# classd.net
KiCad netlist of a schematic drawn in EAGLE
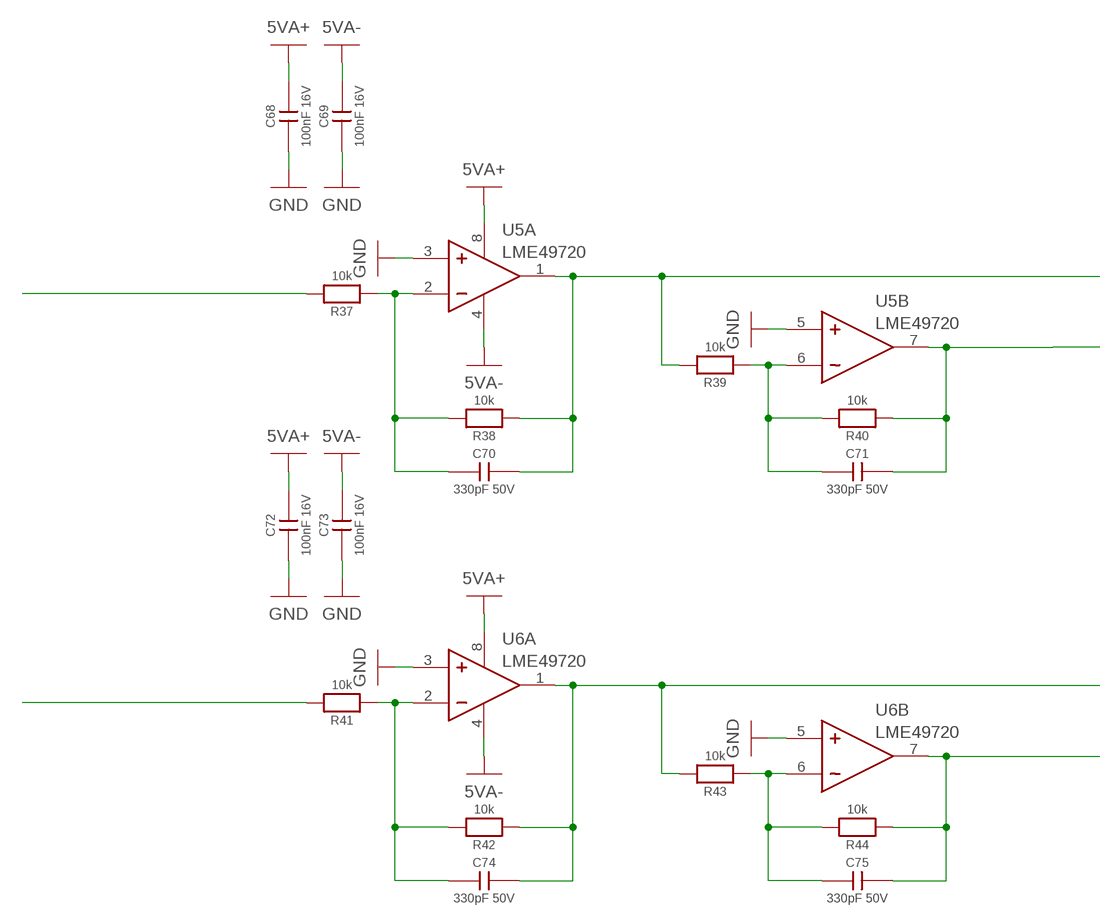
[diagram p0: schematic, sheet 1, part 1 of 2]
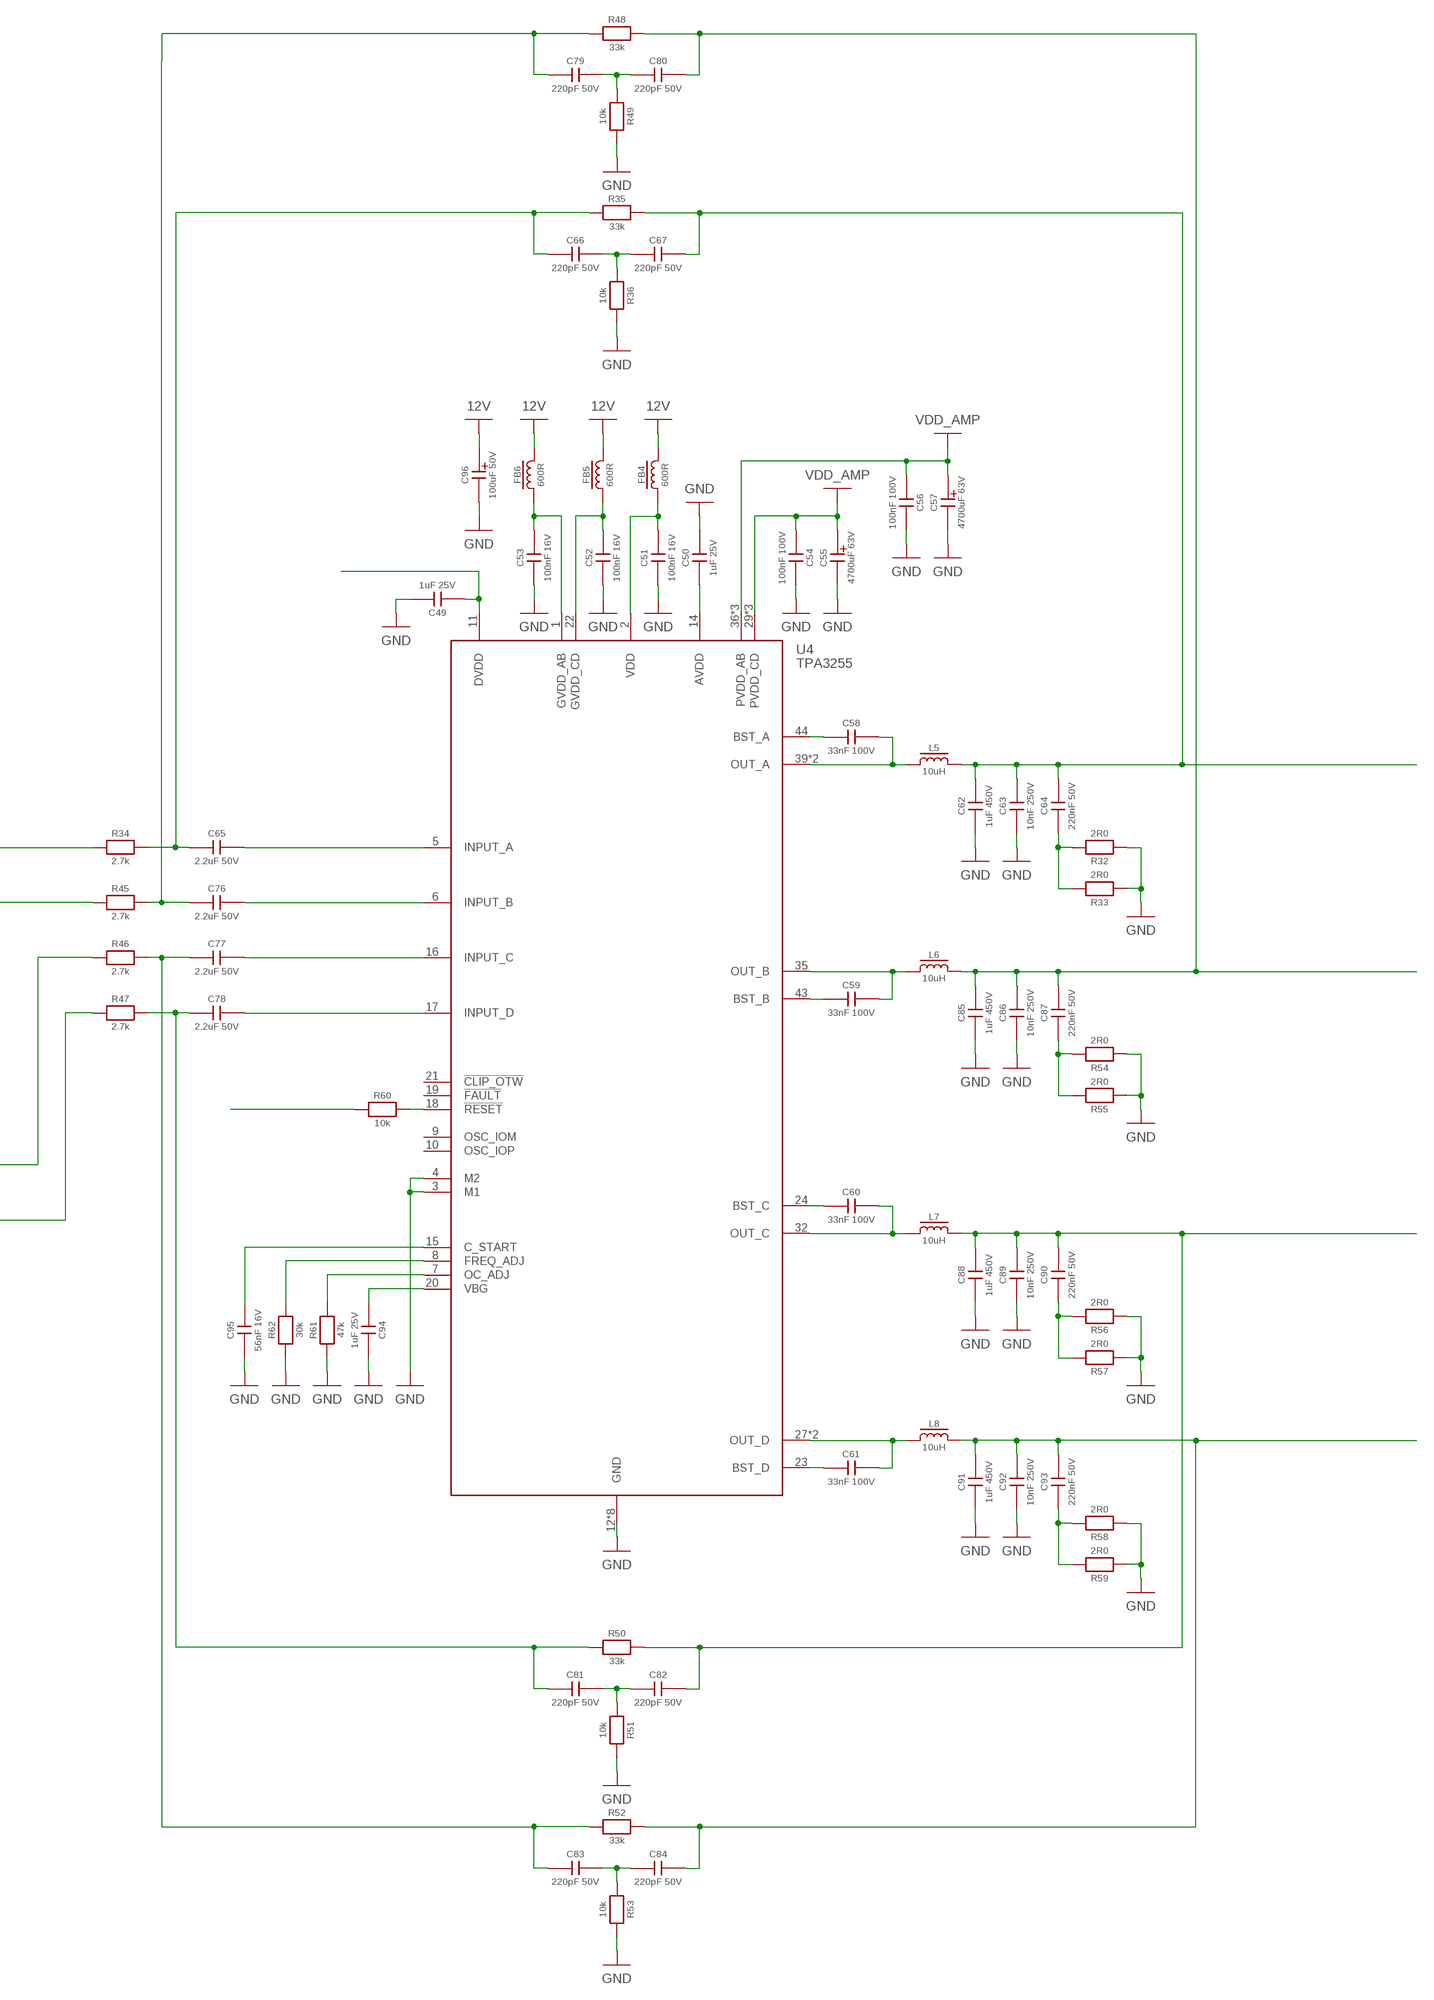
[diagram p1: schematic, sheet 1, part 2 of 2]

(export (version "E")
  (design (tool "Eeschema 10.0.6"))
  (components
    (comp (ref "C49")
      (value "1uF 25V")
      (footprint "eagle-import:0603")
      (libsource (lib "eagle-import") (part "CL10A105KA8NNNC"))
    )
    (comp (ref "C50")
      (value "1uF 25V")
      (footprint "eagle-import:0603")
      (libsource (lib "eagle-import") (part "CL10A105KA8NNNC"))
    )
    (comp (ref "C51")
      (value "100nF 16V")
      (footprint "eagle-import:0603")
      (libsource (lib "eagle-import") (part "CL10B104KO8WPNC"))
    )
    (comp (ref "C52")
      (value "100nF 16V")
      (footprint "eagle-import:0603")
      (libsource (lib "eagle-import") (part "CL10B104KO8WPNC"))
    )
    (comp (ref "C53")
      (value "100nF 16V")
      (footprint "eagle-import:0603")
      (libsource (lib "eagle-import") (part "CL10B104KO8WPNC"))
    )
    (comp (ref "C54")
      (value "100nF 100V")
      (footprint "eagle-import:0603")
      (libsource (lib "eagle-import") (part "06031C104KAT2A"))
    )
    (comp (ref "C55")
      (value "4700uF 63V")
      (footprint "eagle-import:30MM_RADIAL_10MM_PITCH")
      (libsource (lib "eagle-import") (part "B41231C8478M000"))
    )
    (comp (ref "C56")
      (value "100nF 100V")
      (footprint "eagle-import:0603")
      (libsource (lib "eagle-import") (part "06031C104KAT2A"))
    )
    (comp (ref "C57")
      (value "4700uF 63V")
      (footprint "eagle-import:30MM_RADIAL_10MM_PITCH")
      (libsource (lib "eagle-import") (part "B41231C8478M000"))
    )
    (comp (ref "C58")
      (value "33nF 100V")
      (footprint "eagle-import:0603")
      (libsource (lib "eagle-import") (part "C0603C333K1RACTU"))
    )
    (comp (ref "C59")
      (value "33nF 100V")
      (footprint "eagle-import:0603")
      (libsource (lib "eagle-import") (part "C0603C333K1RACTU"))
    )
    (comp (ref "C60")
      (value "33nF 100V")
      (footprint "eagle-import:0603")
      (libsource (lib "eagle-import") (part "C0603C333K1RACTU"))
    )
    (comp (ref "C61")
      (value "33nF 100V")
      (footprint "eagle-import:0603")
      (libsource (lib "eagle-import") (part "C0603C333K1RACTU"))
    )
    (comp (ref "C62")
      (value "1uF 450V")
      (footprint "eagle-import:7X17.5BOX")
      (libsource (lib "eagle-import") (part "ECWFE2W105K"))
    )
    (comp (ref "C63")
      (value "10nF 250V")
      (footprint "eagle-import:0603")
      (libsource (lib "eagle-import") (part "885342206006"))
    )
    (comp (ref "C64")
      (value "220nF 50V")
      (footprint "eagle-import:0603")
      (libsource (lib "eagle-import") (part "C1608X7R1H224K080AB"))
    )
    (comp (ref "C65")
      (value "2.2uF 50V")
      (footprint "eagle-import:5X7.2BOX")
      (libsource (lib "eagle-import") (part "MKS2B042201F00KSSD"))
    )
    (comp (ref "C66")
      (value "220pF 50V")
      (footprint "eagle-import:0603")
      (libsource (lib "eagle-import") (part "CC0603JRNPO9BN221"))
    )
    (comp (ref "C67")
      (value "220pF 50V")
      (footprint "eagle-import:0603")
      (libsource (lib "eagle-import") (part "CC0603JRNPO9BN221"))
    )
    (comp (ref "C68")
      (value "100nF 16V")
      (footprint "eagle-import:0603")
      (libsource (lib "eagle-import") (part "CL10B104KO8WPNC"))
    )
    (comp (ref "C69")
      (value "100nF 16V")
      (footprint "eagle-import:0603")
      (libsource (lib "eagle-import") (part "CL10B104KO8WPNC"))
    )
    (comp (ref "C70")
      (value "330pF 50V")
      (footprint "eagle-import:0603")
      (libsource (lib "eagle-import") (part "CC0603JRNPO9BN331"))
    )
    (comp (ref "C71")
      (value "330pF 50V")
      (footprint "eagle-import:0603")
      (libsource (lib "eagle-import") (part "CC0603JRNPO9BN331"))
    )
    (comp (ref "C72")
      (value "100nF 16V")
      (footprint "eagle-import:0603")
      (libsource (lib "eagle-import") (part "CL10B104KO8WPNC"))
    )
    (comp (ref "C73")
      (value "100nF 16V")
      (footprint "eagle-import:0603")
      (libsource (lib "eagle-import") (part "CL10B104KO8WPNC"))
    )
    (comp (ref "C74")
      (value "330pF 50V")
      (footprint "eagle-import:0603")
      (libsource (lib "eagle-import") (part "CC0603JRNPO9BN331"))
    )
    (comp (ref "C75")
      (value "330pF 50V")
      (footprint "eagle-import:0603")
      (libsource (lib "eagle-import") (part "CC0603JRNPO9BN331"))
    )
    (comp (ref "C76")
      (value "2.2uF 50V")
      (footprint "eagle-import:5X7.2BOX")
      (libsource (lib "eagle-import") (part "MKS2B042201F00KSSD"))
    )
    (comp (ref "C77")
      (value "2.2uF 50V")
      (footprint "eagle-import:5X7.2BOX")
      (libsource (lib "eagle-import") (part "MKS2B042201F00KSSD"))
    )
    (comp (ref "C78")
      (value "2.2uF 50V")
      (footprint "eagle-import:5X7.2BOX")
      (libsource (lib "eagle-import") (part "MKS2B042201F00KSSD"))
    )
    (comp (ref "C79")
      (value "220pF 50V")
      (footprint "eagle-import:0603")
      (libsource (lib "eagle-import") (part "CC0603JRNPO9BN221"))
    )
    (comp (ref "C80")
      (value "220pF 50V")
      (footprint "eagle-import:0603")
      (libsource (lib "eagle-import") (part "CC0603JRNPO9BN221"))
    )
    (comp (ref "C81")
      (value "220pF 50V")
      (footprint "eagle-import:0603")
      (libsource (lib "eagle-import") (part "CC0603JRNPO9BN221"))
    )
    (comp (ref "C82")
      (value "220pF 50V")
      (footprint "eagle-import:0603")
      (libsource (lib "eagle-import") (part "CC0603JRNPO9BN221"))
    )
    (comp (ref "C83")
      (value "220pF 50V")
      (footprint "eagle-import:0603")
      (libsource (lib "eagle-import") (part "CC0603JRNPO9BN221"))
    )
    (comp (ref "C84")
      (value "220pF 50V")
      (footprint "eagle-import:0603")
      (libsource (lib "eagle-import") (part "CC0603JRNPO9BN221"))
    )
    (comp (ref "C85")
      (value "1uF 450V")
      (footprint "eagle-import:7X17.5BOX")
      (libsource (lib "eagle-import") (part "ECWFE2W105K"))
    )
    (comp (ref "C86")
      (value "10nF 250V")
      (footprint "eagle-import:0603")
      (libsource (lib "eagle-import") (part "885342206006"))
    )
    (comp (ref "C87")
      (value "220nF 50V")
      (footprint "eagle-import:0603")
      (libsource (lib "eagle-import") (part "C1608X7R1H224K080AB"))
    )
    (comp (ref "C88")
      (value "1uF 450V")
      (footprint "eagle-import:7X17.5BOX")
      (libsource (lib "eagle-import") (part "ECWFE2W105K"))
    )
    (comp (ref "C89")
      (value "10nF 250V")
      (footprint "eagle-import:0603")
      (libsource (lib "eagle-import") (part "885342206006"))
    )
    (comp (ref "C90")
      (value "220nF 50V")
      (footprint "eagle-import:0603")
      (libsource (lib "eagle-import") (part "C1608X7R1H224K080AB"))
    )
    (comp (ref "C91")
      (value "1uF 450V")
      (footprint "eagle-import:7X17.5BOX")
      (libsource (lib "eagle-import") (part "ECWFE2W105K"))
    )
    (comp (ref "C92")
      (value "10nF 250V")
      (footprint "eagle-import:0603")
      (libsource (lib "eagle-import") (part "885342206006"))
    )
    (comp (ref "C93")
      (value "220nF 50V")
      (footprint "eagle-import:0603")
      (libsource (lib "eagle-import") (part "C1608X7R1H224K080AB"))
    )
    (comp (ref "C94")
      (value "1uF 25V")
      (footprint "eagle-import:0603")
      (libsource (lib "eagle-import") (part "CL10A105KA8NNNC"))
    )
    (comp (ref "C95")
      (value "56nF 16V")
      (footprint "eagle-import:0603")
      (libsource (lib "eagle-import") (part "GRM188R71C563JA01D"))
    )
    (comp (ref "C96")
      (value "100uF 50V")
      (footprint "eagle-import:8MM_RADIAL_3.5MM_PITCH")
      (libsource (lib "eagle-import") (part "107CKR050M"))
    )
    (comp (ref "FB4")
      (value "600R")
      (footprint "eagle-import:0603")
      (libsource (lib "eagle-import") (part "742792651"))
    )
    (comp (ref "FB5")
      (value "600R")
      (footprint "eagle-import:0603")
      (libsource (lib "eagle-import") (part "742792651"))
    )
    (comp (ref "FB6")
      (value "600R")
      (footprint "eagle-import:0603")
      (libsource (lib "eagle-import") (part "742792651"))
    )
    (comp (ref "L5")
      (value "10uH")
      (footprint "eagle-import:SRP1265A")
      (libsource (lib "eagle-import") (part "SRP1265A-100M"))
    )
    (comp (ref "L6")
      (value "10uH")
      (footprint "eagle-import:SRP1265A")
      (libsource (lib "eagle-import") (part "SRP1265A-100M"))
    )
    (comp (ref "L7")
      (value "10uH")
      (footprint "eagle-import:SRP1265A")
      (libsource (lib "eagle-import") (part "SRP1265A-100M"))
    )
    (comp (ref "L8")
      (value "10uH")
      (footprint "eagle-import:SRP1265A")
      (libsource (lib "eagle-import") (part "SRP1265A-100M"))
    )
    (comp (ref "R32")
      (value "2R0")
      (footprint "eagle-import:1206")
      (libsource (lib "eagle-import") (part "CRCW12062R00FNEA"))
    )
    (comp (ref "R33")
      (value "2R0")
      (footprint "eagle-import:1206")
      (libsource (lib "eagle-import") (part "CRCW12062R00FNEA"))
    )
    (comp (ref "R34")
      (value "2.7k")
      (footprint "eagle-import:0603")
      (libsource (lib "eagle-import") (part "ERJ3EKF2701V"))
    )
    (comp (ref "R35")
      (value "33k")
      (footprint "eagle-import:0603")
      (libsource (lib "eagle-import") (part "ERJ3EKF3302V"))
    )
    (comp (ref "R36")
      (value "10k")
      (footprint "eagle-import:0603")
      (libsource (lib "eagle-import") (part "ERJ3EKF1002V"))
    )
    (comp (ref "R37")
      (value "10k")
      (footprint "eagle-import:0603")
      (libsource (lib "eagle-import") (part "ERJ3EKF1002V"))
    )
    (comp (ref "R38")
      (value "10k")
      (footprint "eagle-import:0603")
      (libsource (lib "eagle-import") (part "ERJ3EKF1002V"))
    )
    (comp (ref "R39")
      (value "10k")
      (footprint "eagle-import:0603")
      (libsource (lib "eagle-import") (part "ERJ3EKF1002V"))
    )
    (comp (ref "R40")
      (value "10k")
      (footprint "eagle-import:0603")
      (libsource (lib "eagle-import") (part "ERJ3EKF1002V"))
    )
    (comp (ref "R41")
      (value "10k")
      (footprint "eagle-import:0603")
      (libsource (lib "eagle-import") (part "ERJ3EKF1002V"))
    )
    (comp (ref "R42")
      (value "10k")
      (footprint "eagle-import:0603")
      (libsource (lib "eagle-import") (part "ERJ3EKF1002V"))
    )
    (comp (ref "R43")
      (value "10k")
      (footprint "eagle-import:0603")
      (libsource (lib "eagle-import") (part "ERJ3EKF1002V"))
    )
    (comp (ref "R44")
      (value "10k")
      (footprint "eagle-import:0603")
      (libsource (lib "eagle-import") (part "ERJ3EKF1002V"))
    )
    (comp (ref "R45")
      (value "2.7k")
      (footprint "eagle-import:0603")
      (libsource (lib "eagle-import") (part "ERJ3EKF2701V"))
    )
    (comp (ref "R46")
      (value "2.7k")
      (footprint "eagle-import:0603")
      (libsource (lib "eagle-import") (part "ERJ3EKF2701V"))
    )
    (comp (ref "R47")
      (value "2.7k")
      (footprint "eagle-import:0603")
      (libsource (lib "eagle-import") (part "ERJ3EKF2701V"))
    )
    (comp (ref "R48")
      (value "33k")
      (footprint "eagle-import:0603")
      (libsource (lib "eagle-import") (part "ERJ3EKF3302V"))
    )
    (comp (ref "R49")
      (value "10k")
      (footprint "eagle-import:0603")
      (libsource (lib "eagle-import") (part "ERJ3EKF1002V"))
    )
    (comp (ref "R50")
      (value "33k")
      (footprint "eagle-import:0603")
      (libsource (lib "eagle-import") (part "ERJ3EKF3302V"))
    )
    (comp (ref "R51")
      (value "10k")
      (footprint "eagle-import:0603")
      (libsource (lib "eagle-import") (part "ERJ3EKF1002V"))
    )
    (comp (ref "R52")
      (value "33k")
      (footprint "eagle-import:0603")
      (libsource (lib "eagle-import") (part "ERJ3EKF3302V"))
    )
    (comp (ref "R53")
      (value "10k")
      (footprint "eagle-import:0603")
      (libsource (lib "eagle-import") (part "ERJ3EKF1002V"))
    )
    (comp (ref "R54")
      (value "2R0")
      (footprint "eagle-import:1206")
      (libsource (lib "eagle-import") (part "CRCW12062R00FNEA"))
    )
    (comp (ref "R55")
      (value "2R0")
      (footprint "eagle-import:1206")
      (libsource (lib "eagle-import") (part "CRCW12062R00FNEA"))
    )
    (comp (ref "R56")
      (value "2R0")
      (footprint "eagle-import:1206")
      (libsource (lib "eagle-import") (part "CRCW12062R00FNEA"))
    )
    (comp (ref "R57")
      (value "2R0")
      (footprint "eagle-import:1206")
      (libsource (lib "eagle-import") (part "CRCW12062R00FNEA"))
    )
    (comp (ref "R58")
      (value "2R0")
      (footprint "eagle-import:1206")
      (libsource (lib "eagle-import") (part "CRCW12062R00FNEA"))
    )
    (comp (ref "R59")
      (value "2R0")
      (footprint "eagle-import:1206")
      (libsource (lib "eagle-import") (part "CRCW12062R00FNEA"))
    )
    (comp (ref "R60")
      (value "10k")
      (footprint "eagle-import:0603")
      (libsource (lib "eagle-import") (part "ERJ3EKF1002V"))
    )
    (comp (ref "R61")
      (value "47k")
      (footprint "eagle-import:0603")
      (libsource (lib "eagle-import") (part "ERJ3EKF4702V"))
    )
    (comp (ref "R62")
      (value "30k")
      (footprint "eagle-import:0603")
      (libsource (lib "eagle-import") (part "ERJ3EKF3002V"))
    )
    (comp (ref "U4")
      (value "TPA3255")
      (footprint "eagle-import:HTSSOP44")
      (libsource (lib "eagle-import") (part "TPA3255"))
    )
    (comp (ref "U5")
      (value "LME49720")
      (footprint "eagle-import:SO8")
      (libsource (lib "eagle-import") (part "LME49720MA/NOPB"))
    )
    (comp (ref "U6")
      (value "LME49720")
      (footprint "eagle-import:SO8")
      (libsource (lib "eagle-import") (part "LME49720MA/NOPB"))
    )
  )
  (nets
    (net (code "1") (name "/TPA_VDD_1") (class "Default")
      (node (ref "C49") (pin "1") (pinfunction "1_1") (pintype "bidirectional"))
      (node (ref "R60") (pin "1") (pinfunction "1_1") (pintype "bidirectional"))
      (node (ref "U4") (pin "11") (pinfunction "DVDD_11") (pintype "bidirectional"))
    )
    (net (code "2") (name "5VA+") (class "Default")
      (node (ref "C68") (pin "2") (pinfunction "2_2") (pintype "bidirectional"))
      (node (ref "C72") (pin "2") (pinfunction "2_2") (pintype "bidirectional"))
      (node (ref "U5") (pin "8") (pinfunction "V+_8") (pintype "bidirectional"))
      (node (ref "U6") (pin "8") (pinfunction "V+_8") (pintype "bidirectional"))
    )
    (net (code "3") (name "5VA-") (class "Default")
      (node (ref "C69") (pin "2") (pinfunction "2_2") (pintype "bidirectional"))
      (node (ref "C73") (pin "2") (pinfunction "2_2") (pintype "bidirectional"))
      (node (ref "U5") (pin "4") (pinfunction "V-_4") (pintype "bidirectional"))
      (node (ref "U6") (pin "4") (pinfunction "V-_4") (pintype "bidirectional"))
    )
    (net (code "4") (name "12V") (class "Default")
      (node (ref "C96") (pin "P") (pinfunction "A_P") (pintype "bidirectional"))
      (node (ref "FB4") (pin "2") (pinfunction "2_2") (pintype "bidirectional"))
      (node (ref "FB5") (pin "2") (pinfunction "2_2") (pintype "bidirectional"))
      (node (ref "FB6") (pin "2") (pinfunction "2_2") (pintype "bidirectional"))
    )
    (net (code "5") (name "GND") (class "Default")
      (node (ref "C49") (pin "2") (pinfunction "2_2") (pintype "bidirectional"))
      (node (ref "C50") (pin "2") (pinfunction "2_2") (pintype "bidirectional"))
      (node (ref "C51") (pin "1") (pinfunction "1_1") (pintype "bidirectional"))
      (node (ref "C52") (pin "1") (pinfunction "1_1") (pintype "bidirectional"))
      (node (ref "C53") (pin "1") (pinfunction "1_1") (pintype "bidirectional"))
      (node (ref "C54") (pin "2") (pinfunction "2_2") (pintype "bidirectional"))
      (node (ref "C55") (pin "1") (pinfunction "K_1") (pintype "bidirectional"))
      (node (ref "C56") (pin "2") (pinfunction "2_2") (pintype "bidirectional"))
      (node (ref "C57") (pin "1") (pinfunction "K_1") (pintype "bidirectional"))
      (node (ref "C62") (pin "1") (pinfunction "1_1") (pintype "bidirectional"))
      (node (ref "C63") (pin "1") (pinfunction "1_1") (pintype "bidirectional"))
      (node (ref "C68") (pin "1") (pinfunction "1_1") (pintype "bidirectional"))
      (node (ref "C69") (pin "1") (pinfunction "1_1") (pintype "bidirectional"))
      (node (ref "C72") (pin "1") (pinfunction "1_1") (pintype "bidirectional"))
      (node (ref "C73") (pin "1") (pinfunction "1_1") (pintype "bidirectional"))
      (node (ref "C85") (pin "1") (pinfunction "1_1") (pintype "bidirectional"))
      (node (ref "C86") (pin "1") (pinfunction "1_1") (pintype "bidirectional"))
      (node (ref "C88") (pin "1") (pinfunction "1_1") (pintype "bidirectional"))
      (node (ref "C89") (pin "1") (pinfunction "1_1") (pintype "bidirectional"))
      (node (ref "C91") (pin "1") (pinfunction "1_1") (pintype "bidirectional"))
      (node (ref "C92") (pin "1") (pinfunction "1_1") (pintype "bidirectional"))
      (node (ref "C94") (pin "2") (pinfunction "2_2") (pintype "bidirectional"))
      (node (ref "C95") (pin "1") (pinfunction "1_1") (pintype "bidirectional"))
      (node (ref "C96") (pin "N") (pinfunction "K_N") (pintype "bidirectional"))
      (node (ref "R32") (pin "1") (pinfunction "1_1") (pintype "bidirectional"))
      (node (ref "R33") (pin "1") (pinfunction "1_1") (pintype "bidirectional"))
      (node (ref "R36") (pin "2") (pinfunction "2_2") (pintype "bidirectional"))
      (node (ref "R49") (pin "2") (pinfunction "2_2") (pintype "bidirectional"))
      (node (ref "R51") (pin "2") (pinfunction "2_2") (pintype "bidirectional"))
      (node (ref "R53") (pin "2") (pinfunction "2_2") (pintype "bidirectional"))
      (node (ref "R54") (pin "1") (pinfunction "1_1") (pintype "bidirectional"))
      (node (ref "R55") (pin "1") (pinfunction "1_1") (pintype "bidirectional"))
      (node (ref "R56") (pin "1") (pinfunction "1_1") (pintype "bidirectional"))
      (node (ref "R57") (pin "1") (pinfunction "1_1") (pintype "bidirectional"))
      (node (ref "R58") (pin "1") (pinfunction "1_1") (pintype "bidirectional"))
      (node (ref "R59") (pin "1") (pinfunction "1_1") (pintype "bidirectional"))
      (node (ref "R61") (pin "1") (pinfunction "1_1") (pintype "bidirectional"))
      (node (ref "R62") (pin "1") (pinfunction "1_1") (pintype "bidirectional"))
      (node (ref "U4") (pin "12") (pinfunction "GND_12") (pintype "bidirectional"))
      (node (ref "U4") (pin "13") (pinfunction "GND_13") (pintype "bidirectional"))
      (node (ref "U4") (pin "25") (pinfunction "GND_25") (pintype "bidirectional"))
      (node (ref "U4") (pin "26") (pinfunction "GND_26") (pintype "bidirectional"))
      (node (ref "U4") (pin "3") (pinfunction "M1_3") (pintype "bidirectional"))
      (node (ref "U4") (pin "33") (pinfunction "GND_33") (pintype "bidirectional"))
      (node (ref "U4") (pin "34") (pinfunction "GND_34") (pintype "bidirectional"))
      (node (ref "U4") (pin "4") (pinfunction "M2_4") (pintype "bidirectional"))
      (node (ref "U4") (pin "41") (pinfunction "GND_41") (pintype "bidirectional"))
      (node (ref "U4") (pin "42") (pinfunction "GND_42") (pintype "bidirectional"))
      (node (ref "U5") (pin "3") (pinfunction "+_3") (pintype "bidirectional"))
      (node (ref "U5") (pin "5") (pinfunction "+_5") (pintype "bidirectional"))
      (node (ref "U6") (pin "3") (pinfunction "+_3") (pintype "bidirectional"))
      (node (ref "U6") (pin "5") (pinfunction "+_5") (pintype "bidirectional"))
    )
    (net (code "6") (name "Net-(C58-Pad2)") (class "Default")
      (node (ref "C58") (pin "2") (pinfunction "2_2") (pintype "bidirectional"))
      (node (ref "L5") (pin "1") (pinfunction "1_1") (pintype "bidirectional"))
      (node (ref "U4") (pin "39") (pinfunction "OUT_A_39") (pintype "bidirectional"))
      (node (ref "U4") (pin "40") (pinfunction "OUT_A_40") (pintype "bidirectional"))
    )
    (net (code "7") (name "Net-(C61-Pad2)") (class "Default")
      (node (ref "C61") (pin "2") (pinfunction "2_2") (pintype "bidirectional"))
      (node (ref "L8") (pin "1") (pinfunction "1_1") (pintype "bidirectional"))
      (node (ref "U4") (pin "27") (pinfunction "OUT_D_27") (pintype "bidirectional"))
      (node (ref "U4") (pin "28") (pinfunction "OUT_D_28") (pintype "bidirectional"))
    )
    (net (code "8") (name "Net-(C62-Pad2)") (class "Default")
      (node (ref "C62") (pin "2") (pinfunction "2_2") (pintype "bidirectional"))
      (node (ref "C63") (pin "2") (pinfunction "2_2") (pintype "bidirectional"))
      (node (ref "C64") (pin "2") (pinfunction "2_2") (pintype "bidirectional"))
      (node (ref "C67") (pin "2") (pinfunction "2_2") (pintype "bidirectional"))
      (node (ref "L5") (pin "2") (pinfunction "2_2") (pintype "bidirectional"))
      (node (ref "R35") (pin "2") (pinfunction "2_2") (pintype "bidirectional"))
    )
    (net (code "9") (name "Net-(C64-Pad1)") (class "Default")
      (node (ref "C64") (pin "1") (pinfunction "1_1") (pintype "bidirectional"))
      (node (ref "R32") (pin "2") (pinfunction "2_2") (pintype "bidirectional"))
      (node (ref "R33") (pin "2") (pinfunction "2_2") (pintype "bidirectional"))
    )
    (net (code "10") (name "Net-(C65-Pad1)") (class "Default")
      (node (ref "C65") (pin "1") (pinfunction "1_1") (pintype "bidirectional"))
      (node (ref "C66") (pin "1") (pinfunction "1_1") (pintype "bidirectional"))
      (node (ref "R34") (pin "2") (pinfunction "2_2") (pintype "bidirectional"))
      (node (ref "R35") (pin "1") (pinfunction "1_1") (pintype "bidirectional"))
    )
    (net (code "11") (name "Net-(C66-Pad2)") (class "Default")
      (node (ref "C66") (pin "2") (pinfunction "2_2") (pintype "bidirectional"))
      (node (ref "C67") (pin "1") (pinfunction "1_1") (pintype "bidirectional"))
      (node (ref "R36") (pin "1") (pinfunction "1_1") (pintype "bidirectional"))
    )
    (net (code "12") (name "Net-(C76-Pad1)") (class "Default")
      (node (ref "C76") (pin "1") (pinfunction "1_1") (pintype "bidirectional"))
      (node (ref "C79") (pin "1") (pinfunction "1_1") (pintype "bidirectional"))
      (node (ref "R45") (pin "2") (pinfunction "2_2") (pintype "bidirectional"))
      (node (ref "R48") (pin "1") (pinfunction "1_1") (pintype "bidirectional"))
    )
    (net (code "13") (name "Net-(C77-Pad1)") (class "Default")
      (node (ref "C77") (pin "1") (pinfunction "1_1") (pintype "bidirectional"))
      (node (ref "C83") (pin "1") (pinfunction "1_1") (pintype "bidirectional"))
      (node (ref "R46") (pin "2") (pinfunction "2_2") (pintype "bidirectional"))
      (node (ref "R52") (pin "1") (pinfunction "1_1") (pintype "bidirectional"))
    )
    (net (code "14") (name "Net-(C78-Pad1)") (class "Default")
      (node (ref "C78") (pin "1") (pinfunction "1_1") (pintype "bidirectional"))
      (node (ref "C81") (pin "1") (pinfunction "1_1") (pintype "bidirectional"))
      (node (ref "R47") (pin "2") (pinfunction "2_2") (pintype "bidirectional"))
      (node (ref "R50") (pin "1") (pinfunction "1_1") (pintype "bidirectional"))
    )
    (net (code "15") (name "Net-(C79-Pad2)") (class "Default")
      (node (ref "C79") (pin "2") (pinfunction "2_2") (pintype "bidirectional"))
      (node (ref "C80") (pin "1") (pinfunction "1_1") (pintype "bidirectional"))
      (node (ref "R49") (pin "1") (pinfunction "1_1") (pintype "bidirectional"))
    )
    (net (code "16") (name "Net-(C80-Pad2)") (class "Default")
      (node (ref "C80") (pin "2") (pinfunction "2_2") (pintype "bidirectional"))
      (node (ref "C85") (pin "2") (pinfunction "2_2") (pintype "bidirectional"))
      (node (ref "C86") (pin "2") (pinfunction "2_2") (pintype "bidirectional"))
      (node (ref "C87") (pin "2") (pinfunction "2_2") (pintype "bidirectional"))
      (node (ref "L6") (pin "2") (pinfunction "2_2") (pintype "bidirectional"))
      (node (ref "R48") (pin "2") (pinfunction "2_2") (pintype "bidirectional"))
    )
    (net (code "17") (name "Net-(C81-Pad2)") (class "Default")
      (node (ref "C81") (pin "2") (pinfunction "2_2") (pintype "bidirectional"))
      (node (ref "C82") (pin "1") (pinfunction "1_1") (pintype "bidirectional"))
      (node (ref "R51") (pin "1") (pinfunction "1_1") (pintype "bidirectional"))
    )
    (net (code "18") (name "Net-(C82-Pad2)") (class "Default")
      (node (ref "C82") (pin "2") (pinfunction "2_2") (pintype "bidirectional"))
      (node (ref "C88") (pin "2") (pinfunction "2_2") (pintype "bidirectional"))
      (node (ref "C89") (pin "2") (pinfunction "2_2") (pintype "bidirectional"))
      (node (ref "C90") (pin "2") (pinfunction "2_2") (pintype "bidirectional"))
      (node (ref "L7") (pin "2") (pinfunction "2_2") (pintype "bidirectional"))
      (node (ref "R50") (pin "2") (pinfunction "2_2") (pintype "bidirectional"))
    )
    (net (code "19") (name "Net-(C83-Pad2)") (class "Default")
      (node (ref "C83") (pin "2") (pinfunction "2_2") (pintype "bidirectional"))
      (node (ref "C84") (pin "1") (pinfunction "1_1") (pintype "bidirectional"))
      (node (ref "R53") (pin "1") (pinfunction "1_1") (pintype "bidirectional"))
    )
    (net (code "20") (name "Net-(C84-Pad2)") (class "Default")
      (node (ref "C84") (pin "2") (pinfunction "2_2") (pintype "bidirectional"))
      (node (ref "C91") (pin "2") (pinfunction "2_2") (pintype "bidirectional"))
      (node (ref "C92") (pin "2") (pinfunction "2_2") (pintype "bidirectional"))
      (node (ref "C93") (pin "2") (pinfunction "2_2") (pintype "bidirectional"))
      (node (ref "L8") (pin "2") (pinfunction "2_2") (pintype "bidirectional"))
      (node (ref "R52") (pin "2") (pinfunction "2_2") (pintype "bidirectional"))
    )
    (net (code "21") (name "Net-(C87-Pad1)") (class "Default")
      (node (ref "C87") (pin "1") (pinfunction "1_1") (pintype "bidirectional"))
      (node (ref "R54") (pin "2") (pinfunction "2_2") (pintype "bidirectional"))
      (node (ref "R55") (pin "2") (pinfunction "2_2") (pintype "bidirectional"))
    )
    (net (code "22") (name "Net-(C90-Pad1)") (class "Default")
      (node (ref "C90") (pin "1") (pinfunction "1_1") (pintype "bidirectional"))
      (node (ref "R56") (pin "2") (pinfunction "2_2") (pintype "bidirectional"))
      (node (ref "R57") (pin "2") (pinfunction "2_2") (pintype "bidirectional"))
    )
    (net (code "23") (name "Net-(C93-Pad1)") (class "Default")
      (node (ref "C93") (pin "1") (pinfunction "1_1") (pintype "bidirectional"))
      (node (ref "R58") (pin "2") (pinfunction "2_2") (pintype "bidirectional"))
      (node (ref "R59") (pin "2") (pinfunction "2_2") (pintype "bidirectional"))
    )
    (net (code "24") (name "Net-(U4-AVDD)") (class "Default")
      (node (ref "C50") (pin "1") (pinfunction "1_1") (pintype "bidirectional"))
      (node (ref "U4") (pin "14") (pinfunction "AVDD_14") (pintype "bidirectional"))
    )
    (net (code "25") (name "Net-(U4-BST_A)") (class "Default")
      (node (ref "C58") (pin "1") (pinfunction "1_1") (pintype "bidirectional"))
      (node (ref "U4") (pin "44") (pinfunction "BST_A_44") (pintype "bidirectional"))
    )
    (net (code "26") (name "Net-(U4-BST_B)") (class "Default")
      (node (ref "C59") (pin "1") (pinfunction "1_1") (pintype "bidirectional"))
      (node (ref "U4") (pin "43") (pinfunction "BST_B_43") (pintype "bidirectional"))
    )
    (net (code "27") (name "Net-(U4-BST_C)") (class "Default")
      (node (ref "C60") (pin "1") (pinfunction "1_1") (pintype "bidirectional"))
      (node (ref "U4") (pin "24") (pinfunction "BST_C_24") (pintype "bidirectional"))
    )
    (net (code "28") (name "Net-(U4-BST_D)") (class "Default")
      (node (ref "C61") (pin "1") (pinfunction "1_1") (pintype "bidirectional"))
      (node (ref "U4") (pin "23") (pinfunction "BST_D_23") (pintype "bidirectional"))
    )
    (net (code "29") (name "Net-(U4-C_START)") (class "Default")
      (node (ref "C95") (pin "2") (pinfunction "2_2") (pintype "bidirectional"))
      (node (ref "U4") (pin "15") (pinfunction "C_START_15") (pintype "bidirectional"))
    )
    (net (code "30") (name "Net-(U4-FREQ_ADJ)") (class "Default")
      (node (ref "R62") (pin "2") (pinfunction "2_2") (pintype "bidirectional"))
      (node (ref "U4") (pin "8") (pinfunction "FREQ_ADJ_8") (pintype "bidirectional"))
    )
    (net (code "31") (name "Net-(U4-GVDD_AB)") (class "Default")
      (node (ref "C53") (pin "2") (pinfunction "2_2") (pintype "bidirectional"))
      (node (ref "FB6") (pin "1") (pinfunction "1_1") (pintype "bidirectional"))
      (node (ref "U4") (pin "1") (pinfunction "GVDD_AB_1") (pintype "bidirectional"))
    )
    (net (code "32") (name "Net-(U4-GVDD_CD)") (class "Default")
      (node (ref "C52") (pin "2") (pinfunction "2_2") (pintype "bidirectional"))
      (node (ref "FB5") (pin "1") (pinfunction "1_1") (pintype "bidirectional"))
      (node (ref "U4") (pin "22") (pinfunction "GVDD_CD_22") (pintype "bidirectional"))
    )
    (net (code "33") (name "Net-(U4-INPUT_A)") (class "Default")
      (node (ref "C65") (pin "2") (pinfunction "2_2") (pintype "bidirectional"))
      (node (ref "U4") (pin "5") (pinfunction "INPUT_A_5") (pintype "bidirectional"))
    )
    (net (code "34") (name "Net-(U4-INPUT_B)") (class "Default")
      (node (ref "C76") (pin "2") (pinfunction "2_2") (pintype "bidirectional"))
      (node (ref "U4") (pin "6") (pinfunction "INPUT_B_6") (pintype "bidirectional"))
    )
    (net (code "35") (name "Net-(U4-INPUT_C)") (class "Default")
      (node (ref "C77") (pin "2") (pinfunction "2_2") (pintype "bidirectional"))
      (node (ref "U4") (pin "16") (pinfunction "INPUT_C_16") (pintype "bidirectional"))
    )
    (net (code "36") (name "Net-(U4-INPUT_D)") (class "Default")
      (node (ref "C78") (pin "2") (pinfunction "2_2") (pintype "bidirectional"))
      (node (ref "U4") (pin "17") (pinfunction "INPUT_D_17") (pintype "bidirectional"))
    )
    (net (code "37") (name "Net-(U4-OC_ADJ)") (class "Default")
      (node (ref "R61") (pin "2") (pinfunction "2_2") (pintype "bidirectional"))
      (node (ref "U4") (pin "7") (pinfunction "OC_ADJ_7") (pintype "bidirectional"))
    )
    (net (code "38") (name "Net-(U4-OUT_B)") (class "Default")
      (node (ref "C59") (pin "2") (pinfunction "2_2") (pintype "bidirectional"))
      (node (ref "L6") (pin "1") (pinfunction "1_1") (pintype "bidirectional"))
      (node (ref "U4") (pin "35") (pinfunction "OUT_B_35") (pintype "bidirectional"))
    )
    (net (code "39") (name "Net-(U4-OUT_C)") (class "Default")
      (node (ref "C60") (pin "2") (pinfunction "2_2") (pintype "bidirectional"))
      (node (ref "L7") (pin "1") (pinfunction "1_1") (pintype "bidirectional"))
      (node (ref "U4") (pin "32") (pinfunction "OUT_C_32") (pintype "bidirectional"))
    )
    (net (code "40") (name "Net-(U4-VBG)") (class "Default")
      (node (ref "C94") (pin "1") (pinfunction "1_1") (pintype "bidirectional"))
      (node (ref "U4") (pin "20") (pinfunction "VBG_20") (pintype "bidirectional"))
    )
    (net (code "41") (name "Net-(U4-VDD)") (class "Default")
      (node (ref "C51") (pin "2") (pinfunction "2_2") (pintype "bidirectional"))
      (node (ref "FB4") (pin "1") (pinfunction "1_1") (pintype "bidirectional"))
      (node (ref "U4") (pin "2") (pinfunction "VDD_2") (pintype "bidirectional"))
    )
    (net (code "42") (name "Net-(U4-~{RESET})") (class "Default")
      (node (ref "R60") (pin "2") (pinfunction "2_2") (pintype "bidirectional"))
      (node (ref "U4") (pin "18") (pinfunction "~{RESET}_18") (pintype "bidirectional"))
    )
    (net (code "43") (name "Net-(U5A--)") (class "Default")
      (node (ref "C70") (pin "1") (pinfunction "1_1") (pintype "bidirectional"))
      (node (ref "R37") (pin "1") (pinfunction "1_1") (pintype "bidirectional"))
      (node (ref "R38") (pin "2") (pinfunction "2_2") (pintype "bidirectional"))
      (node (ref "U5") (pin "2") (pinfunction "-_2") (pintype "bidirectional"))
    )
    (net (code "44") (name "Net-(U5A-OUT)") (class "Default")
      (node (ref "C70") (pin "2") (pinfunction "2_2") (pintype "bidirectional"))
      (node (ref "R34") (pin "1") (pinfunction "1_1") (pintype "bidirectional"))
      (node (ref "R38") (pin "1") (pinfunction "1_1") (pintype "bidirectional"))
      (node (ref "R39") (pin "2") (pinfunction "2_2") (pintype "bidirectional"))
      (node (ref "U5") (pin "1") (pinfunction "OUT_1") (pintype "bidirectional"))
    )
    (net (code "45") (name "Net-(U5B--)") (class "Default")
      (node (ref "C71") (pin "1") (pinfunction "1_1") (pintype "bidirectional"))
      (node (ref "R39") (pin "1") (pinfunction "1_1") (pintype "bidirectional"))
      (node (ref "R40") (pin "2") (pinfunction "2_2") (pintype "bidirectional"))
      (node (ref "U5") (pin "6") (pinfunction "-_6") (pintype "bidirectional"))
    )
    (net (code "46") (name "Net-(U5B-OUT)") (class "Default")
      (node (ref "C71") (pin "2") (pinfunction "2_2") (pintype "bidirectional"))
      (node (ref "R40") (pin "1") (pinfunction "1_1") (pintype "bidirectional"))
      (node (ref "R45") (pin "1") (pinfunction "1_1") (pintype "bidirectional"))
      (node (ref "U5") (pin "7") (pinfunction "OUT_7") (pintype "bidirectional"))
    )
    (net (code "47") (name "Net-(U6A--)") (class "Default")
      (node (ref "C74") (pin "1") (pinfunction "1_1") (pintype "bidirectional"))
      (node (ref "R41") (pin "1") (pinfunction "1_1") (pintype "bidirectional"))
      (node (ref "R42") (pin "2") (pinfunction "2_2") (pintype "bidirectional"))
      (node (ref "U6") (pin "2") (pinfunction "-_2") (pintype "bidirectional"))
    )
    (net (code "48") (name "Net-(U6A-OUT)") (class "Default")
      (node (ref "C74") (pin "2") (pinfunction "2_2") (pintype "bidirectional"))
      (node (ref "R42") (pin "1") (pinfunction "1_1") (pintype "bidirectional"))
      (node (ref "R43") (pin "2") (pinfunction "2_2") (pintype "bidirectional"))
      (node (ref "R46") (pin "1") (pinfunction "1_1") (pintype "bidirectional"))
      (node (ref "U6") (pin "1") (pinfunction "OUT_1") (pintype "bidirectional"))
    )
    (net (code "49") (name "Net-(U6B--)") (class "Default")
      (node (ref "C75") (pin "1") (pinfunction "1_1") (pintype "bidirectional"))
      (node (ref "R43") (pin "1") (pinfunction "1_1") (pintype "bidirectional"))
      (node (ref "R44") (pin "2") (pinfunction "2_2") (pintype "bidirectional"))
      (node (ref "U6") (pin "6") (pinfunction "-_6") (pintype "bidirectional"))
    )
    (net (code "50") (name "Net-(U6B-OUT)") (class "Default")
      (node (ref "C75") (pin "2") (pinfunction "2_2") (pintype "bidirectional"))
      (node (ref "R44") (pin "1") (pinfunction "1_1") (pintype "bidirectional"))
      (node (ref "R47") (pin "1") (pinfunction "1_1") (pintype "bidirectional"))
      (node (ref "U6") (pin "7") (pinfunction "OUT_7") (pintype "bidirectional"))
    )
    (net (code "51") (name "VDD_AMP") (class "Default")
      (node (ref "C54") (pin "1") (pinfunction "1_1") (pintype "bidirectional"))
      (node (ref "C55") (pin "2") (pinfunction "A_2") (pintype "bidirectional"))
      (node (ref "C56") (pin "1") (pinfunction "1_1") (pintype "bidirectional"))
      (node (ref "C57") (pin "2") (pinfunction "A_2") (pintype "bidirectional"))
      (node (ref "U4") (pin "29") (pinfunction "PVDD_CD_29") (pintype "bidirectional"))
      (node (ref "U4") (pin "30") (pinfunction "PVDD_CD_30") (pintype "bidirectional"))
      (node (ref "U4") (pin "31") (pinfunction "PVDD_CD_31") (pintype "bidirectional"))
      (node (ref "U4") (pin "36") (pinfunction "PVDD_AB_36") (pintype "bidirectional"))
      (node (ref "U4") (pin "37") (pinfunction "PVDD_AB_37") (pintype "bidirectional"))
      (node (ref "U4") (pin "38") (pinfunction "PVDD_AB_38") (pintype "bidirectional"))
    )
    (net (code "52") (name "unconnected-(R37-Pad2)") (class "Default")
      (node (ref "R37") (pin "2") (pinfunction "2_2") (pintype "bidirectional"))
    )
    (net (code "53") (name "unconnected-(R41-Pad2)") (class "Default")
      (node (ref "R41") (pin "2") (pinfunction "2_2") (pintype "bidirectional"))
    )
    (net (code "54") (name "unconnected-(U4-OSC_IOM-Pad9)") (class "Default")
      (node (ref "U4") (pin "9") (pinfunction "OSC_IOM_9") (pintype "bidirectional"))
    )
    (net (code "55") (name "unconnected-(U4-OSC_IOP-Pad10)") (class "Default")
      (node (ref "U4") (pin "10") (pinfunction "OSC_IOP_10") (pintype "bidirectional"))
    )
    (net (code "56") (name "unconnected-(U4-~{CLIP_OTW}-Pad21)") (class "Default")
      (node (ref "U4") (pin "21") (pinfunction "~{CLIP_OTW}_21") (pintype "bidirectional"))
    )
    (net (code "57") (name "unconnected-(U4-~{FAULT}-Pad19)") (class "Default")
      (node (ref "U4") (pin "19") (pinfunction "~{FAULT}_19") (pintype "bidirectional"))
    )
  )
)
